# SensorHub.net
KiCad netlist of a schematic drawn in EAGLE
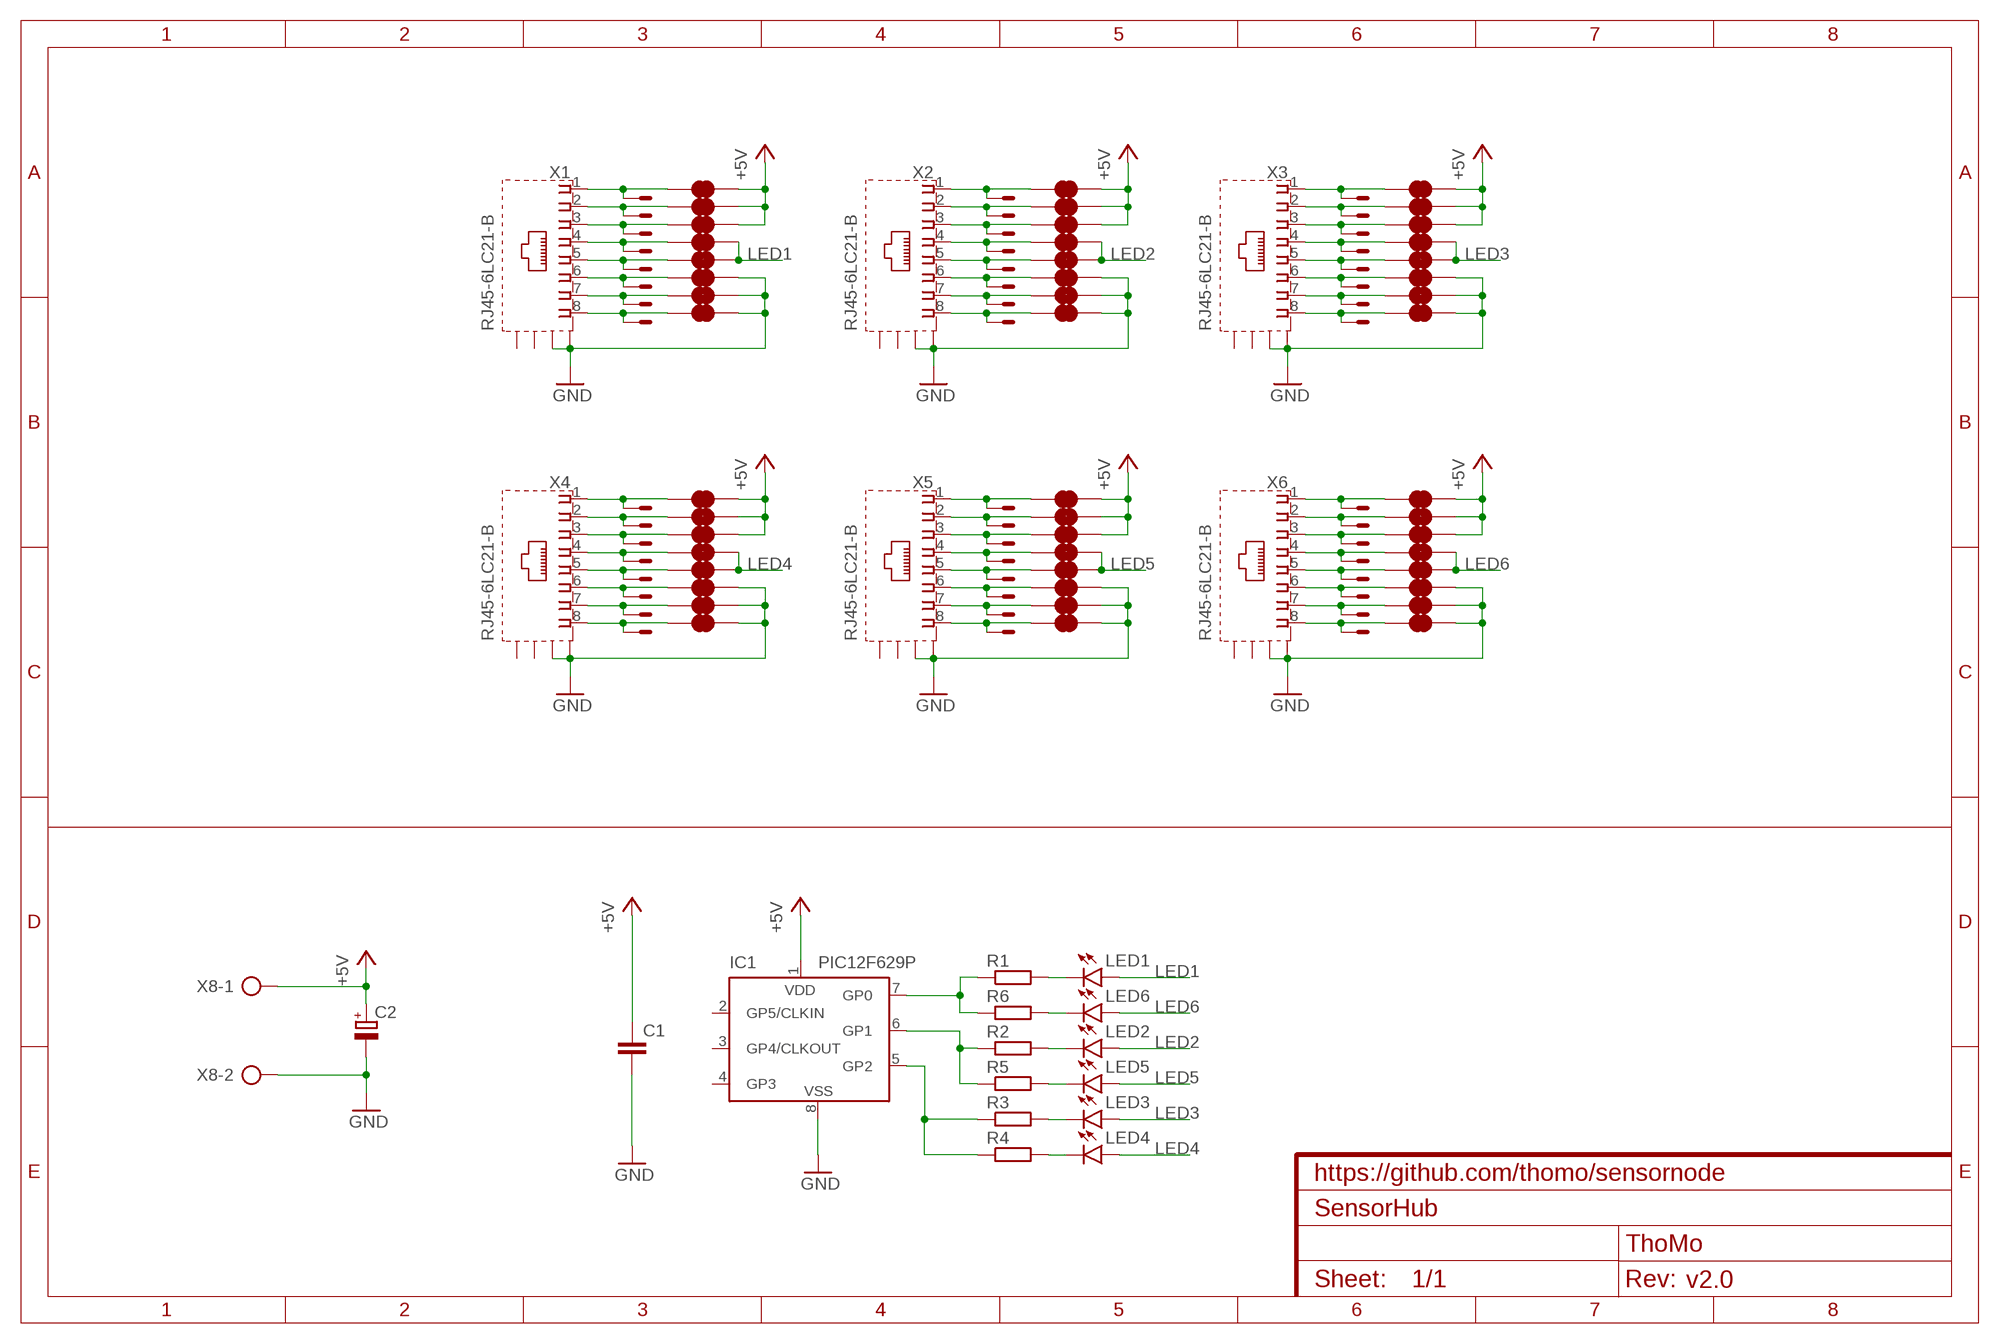
[diagram p0: schematic, sheet 1]

(export (version "E")
  (design (tool "Eeschema 10.0.6"))
  (components
    (comp (ref "C1")
      (value "C-EU050-024X044")
      (footprint "eagle-import:C050-024X044")
      (libsource (lib "eagle-import") (part "C-EU050-024X044"))
    )
    (comp (ref "C2")
      (value "CPOL-EUE3.5-8")
      (footprint "eagle-import:E3,5-8")
      (libsource (lib "eagle-import") (part "CPOL-EUE3.5-8"))
    )
    (comp (ref "IC1")
      (value "PIC12F629P")
      (footprint "eagle-import:DIL8")
      (fields (field (name "MF") "MICROCHIP") (field (name "MPN") "PIC12F629-I/P"))
      (libsource (lib "eagle-import") (part "PIC12F6P29"))
    )
    (comp (ref "JP1")
      (value "JUMPER-SMT_2_NC_TRACE_SILK")
      (footprint "eagle-import:SMT-JUMPER_2_NC_TRACE_SILK")
      (libsource (lib "eagle-import") (part "JUMPER-SMT_2_NC_TRACE_SILK"))
    )
    (comp (ref "JP2")
      (value "JUMPER-SMT_2_NC_TRACE_SILK")
      (footprint "eagle-import:SMT-JUMPER_2_NC_TRACE_SILK")
      (libsource (lib "eagle-import") (part "JUMPER-SMT_2_NC_TRACE_SILK"))
    )
    (comp (ref "JP3")
      (value "JUMPER-SMT_2_NC_TRACE_SILK")
      (footprint "eagle-import:SMT-JUMPER_2_NC_TRACE_SILK")
      (libsource (lib "eagle-import") (part "JUMPER-SMT_2_NC_TRACE_SILK"))
    )
    (comp (ref "JP4")
      (value "JUMPER-SMT_2_NC_TRACE_SILK")
      (footprint "eagle-import:SMT-JUMPER_2_NC_TRACE_SILK")
      (libsource (lib "eagle-import") (part "JUMPER-SMT_2_NC_TRACE_SILK"))
    )
    (comp (ref "JP5")
      (value "JUMPER-SMT_2_NC_TRACE_SILK")
      (footprint "eagle-import:SMT-JUMPER_2_NC_TRACE_SILK")
      (libsource (lib "eagle-import") (part "JUMPER-SMT_2_NC_TRACE_SILK"))
    )
    (comp (ref "JP6")
      (value "JUMPER-SMT_2_NC_TRACE_SILK")
      (footprint "eagle-import:SMT-JUMPER_2_NC_TRACE_SILK")
      (libsource (lib "eagle-import") (part "JUMPER-SMT_2_NC_TRACE_SILK"))
    )
    (comp (ref "JP7")
      (value "JUMPER-SMT_2_NC_TRACE_SILK")
      (footprint "eagle-import:SMT-JUMPER_2_NC_TRACE_SILK")
      (libsource (lib "eagle-import") (part "JUMPER-SMT_2_NC_TRACE_SILK"))
    )
    (comp (ref "JP8")
      (value "JUMPER-SMT_2_NC_TRACE_SILK")
      (footprint "eagle-import:SMT-JUMPER_2_NC_TRACE_SILK")
      (libsource (lib "eagle-import") (part "JUMPER-SMT_2_NC_TRACE_SILK"))
    )
    (comp (ref "JP9")
      (value "JUMPER-SMT_2_NC_TRACE_SILK")
      (footprint "eagle-import:SMT-JUMPER_2_NC_TRACE_SILK")
      (libsource (lib "eagle-import") (part "JUMPER-SMT_2_NC_TRACE_SILK"))
    )
    (comp (ref "JP10")
      (value "JUMPER-SMT_2_NC_TRACE_SILK")
      (footprint "eagle-import:SMT-JUMPER_2_NC_TRACE_SILK")
      (libsource (lib "eagle-import") (part "JUMPER-SMT_2_NC_TRACE_SILK"))
    )
    (comp (ref "JP11")
      (value "JUMPER-SMT_2_NC_TRACE_SILK")
      (footprint "eagle-import:SMT-JUMPER_2_NC_TRACE_SILK")
      (libsource (lib "eagle-import") (part "JUMPER-SMT_2_NC_TRACE_SILK"))
    )
    (comp (ref "JP12")
      (value "JUMPER-SMT_2_NC_TRACE_SILK")
      (footprint "eagle-import:SMT-JUMPER_2_NC_TRACE_SILK")
      (libsource (lib "eagle-import") (part "JUMPER-SMT_2_NC_TRACE_SILK"))
    )
    (comp (ref "JP13")
      (value "JUMPER-SMT_2_NC_TRACE_SILK")
      (footprint "eagle-import:SMT-JUMPER_2_NC_TRACE_SILK")
      (libsource (lib "eagle-import") (part "JUMPER-SMT_2_NC_TRACE_SILK"))
    )
    (comp (ref "JP14")
      (value "JUMPER-SMT_2_NC_TRACE_SILK")
      (footprint "eagle-import:SMT-JUMPER_2_NC_TRACE_SILK")
      (libsource (lib "eagle-import") (part "JUMPER-SMT_2_NC_TRACE_SILK"))
    )
    (comp (ref "JP15")
      (value "JUMPER-SMT_2_NC_TRACE_SILK")
      (footprint "eagle-import:SMT-JUMPER_2_NC_TRACE_SILK")
      (libsource (lib "eagle-import") (part "JUMPER-SMT_2_NC_TRACE_SILK"))
    )
    (comp (ref "JP16")
      (value "JUMPER-SMT_2_NC_TRACE_SILK")
      (footprint "eagle-import:SMT-JUMPER_2_NC_TRACE_SILK")
      (libsource (lib "eagle-import") (part "JUMPER-SMT_2_NC_TRACE_SILK"))
    )
    (comp (ref "JP17")
      (value "JUMPER-SMT_2_NC_TRACE_SILK")
      (footprint "eagle-import:SMT-JUMPER_2_NC_TRACE_SILK")
      (libsource (lib "eagle-import") (part "JUMPER-SMT_2_NC_TRACE_SILK"))
    )
    (comp (ref "JP18")
      (value "JUMPER-SMT_2_NC_TRACE_SILK")
      (footprint "eagle-import:SMT-JUMPER_2_NC_TRACE_SILK")
      (libsource (lib "eagle-import") (part "JUMPER-SMT_2_NC_TRACE_SILK"))
    )
    (comp (ref "JP19")
      (value "JUMPER-SMT_2_NC_TRACE_SILK")
      (footprint "eagle-import:SMT-JUMPER_2_NC_TRACE_SILK")
      (libsource (lib "eagle-import") (part "JUMPER-SMT_2_NC_TRACE_SILK"))
    )
    (comp (ref "JP20")
      (value "JUMPER-SMT_2_NC_TRACE_SILK")
      (footprint "eagle-import:SMT-JUMPER_2_NC_TRACE_SILK")
      (libsource (lib "eagle-import") (part "JUMPER-SMT_2_NC_TRACE_SILK"))
    )
    (comp (ref "JP21")
      (value "JUMPER-SMT_2_NC_TRACE_SILK")
      (footprint "eagle-import:SMT-JUMPER_2_NC_TRACE_SILK")
      (libsource (lib "eagle-import") (part "JUMPER-SMT_2_NC_TRACE_SILK"))
    )
    (comp (ref "JP22")
      (value "JUMPER-SMT_2_NC_TRACE_SILK")
      (footprint "eagle-import:SMT-JUMPER_2_NC_TRACE_SILK")
      (libsource (lib "eagle-import") (part "JUMPER-SMT_2_NC_TRACE_SILK"))
    )
    (comp (ref "JP23")
      (value "JUMPER-SMT_2_NC_TRACE_SILK")
      (footprint "eagle-import:SMT-JUMPER_2_NC_TRACE_SILK")
      (libsource (lib "eagle-import") (part "JUMPER-SMT_2_NC_TRACE_SILK"))
    )
    (comp (ref "JP24")
      (value "JUMPER-SMT_2_NC_TRACE_SILK")
      (footprint "eagle-import:SMT-JUMPER_2_NC_TRACE_SILK")
      (libsource (lib "eagle-import") (part "JUMPER-SMT_2_NC_TRACE_SILK"))
    )
    (comp (ref "JP25")
      (value "JUMPER-SMT_2_NC_TRACE_SILK")
      (footprint "eagle-import:SMT-JUMPER_2_NC_TRACE_SILK")
      (libsource (lib "eagle-import") (part "JUMPER-SMT_2_NC_TRACE_SILK"))
    )
    (comp (ref "JP26")
      (value "JUMPER-SMT_2_NC_TRACE_SILK")
      (footprint "eagle-import:SMT-JUMPER_2_NC_TRACE_SILK")
      (libsource (lib "eagle-import") (part "JUMPER-SMT_2_NC_TRACE_SILK"))
    )
    (comp (ref "JP27")
      (value "JUMPER-SMT_2_NC_TRACE_SILK")
      (footprint "eagle-import:SMT-JUMPER_2_NC_TRACE_SILK")
      (libsource (lib "eagle-import") (part "JUMPER-SMT_2_NC_TRACE_SILK"))
    )
    (comp (ref "JP28")
      (value "JUMPER-SMT_2_NC_TRACE_SILK")
      (footprint "eagle-import:SMT-JUMPER_2_NC_TRACE_SILK")
      (libsource (lib "eagle-import") (part "JUMPER-SMT_2_NC_TRACE_SILK"))
    )
    (comp (ref "JP29")
      (value "JUMPER-SMT_2_NC_TRACE_SILK")
      (footprint "eagle-import:SMT-JUMPER_2_NC_TRACE_SILK")
      (libsource (lib "eagle-import") (part "JUMPER-SMT_2_NC_TRACE_SILK"))
    )
    (comp (ref "JP30")
      (value "JUMPER-SMT_2_NC_TRACE_SILK")
      (footprint "eagle-import:SMT-JUMPER_2_NC_TRACE_SILK")
      (libsource (lib "eagle-import") (part "JUMPER-SMT_2_NC_TRACE_SILK"))
    )
    (comp (ref "JP31")
      (value "JUMPER-SMT_2_NC_TRACE_SILK")
      (footprint "eagle-import:SMT-JUMPER_2_NC_TRACE_SILK")
      (libsource (lib "eagle-import") (part "JUMPER-SMT_2_NC_TRACE_SILK"))
    )
    (comp (ref "JP32")
      (value "JUMPER-SMT_2_NC_TRACE_SILK")
      (footprint "eagle-import:SMT-JUMPER_2_NC_TRACE_SILK")
      (libsource (lib "eagle-import") (part "JUMPER-SMT_2_NC_TRACE_SILK"))
    )
    (comp (ref "JP33")
      (value "JUMPER-SMT_2_NC_TRACE_SILK")
      (footprint "eagle-import:SMT-JUMPER_2_NC_TRACE_SILK")
      (libsource (lib "eagle-import") (part "JUMPER-SMT_2_NC_TRACE_SILK"))
    )
    (comp (ref "JP34")
      (value "JUMPER-SMT_2_NC_TRACE_SILK")
      (footprint "eagle-import:SMT-JUMPER_2_NC_TRACE_SILK")
      (libsource (lib "eagle-import") (part "JUMPER-SMT_2_NC_TRACE_SILK"))
    )
    (comp (ref "JP35")
      (value "JUMPER-SMT_2_NC_TRACE_SILK")
      (footprint "eagle-import:SMT-JUMPER_2_NC_TRACE_SILK")
      (libsource (lib "eagle-import") (part "JUMPER-SMT_2_NC_TRACE_SILK"))
    )
    (comp (ref "JP36")
      (value "JUMPER-SMT_2_NC_TRACE_SILK")
      (footprint "eagle-import:SMT-JUMPER_2_NC_TRACE_SILK")
      (libsource (lib "eagle-import") (part "JUMPER-SMT_2_NC_TRACE_SILK"))
    )
    (comp (ref "JP37")
      (value "JUMPER-SMT_2_NC_TRACE_SILK")
      (footprint "eagle-import:SMT-JUMPER_2_NC_TRACE_SILK")
      (libsource (lib "eagle-import") (part "JUMPER-SMT_2_NC_TRACE_SILK"))
    )
    (comp (ref "JP38")
      (value "JUMPER-SMT_2_NC_TRACE_SILK")
      (footprint "eagle-import:SMT-JUMPER_2_NC_TRACE_SILK")
      (libsource (lib "eagle-import") (part "JUMPER-SMT_2_NC_TRACE_SILK"))
    )
    (comp (ref "JP39")
      (value "JUMPER-SMT_2_NC_TRACE_SILK")
      (footprint "eagle-import:SMT-JUMPER_2_NC_TRACE_SILK")
      (libsource (lib "eagle-import") (part "JUMPER-SMT_2_NC_TRACE_SILK"))
    )
    (comp (ref "JP40")
      (value "JUMPER-SMT_2_NC_TRACE_SILK")
      (footprint "eagle-import:SMT-JUMPER_2_NC_TRACE_SILK")
      (libsource (lib "eagle-import") (part "JUMPER-SMT_2_NC_TRACE_SILK"))
    )
    (comp (ref "JP41")
      (value "JUMPER-SMT_2_NC_TRACE_SILK")
      (footprint "eagle-import:SMT-JUMPER_2_NC_TRACE_SILK")
      (libsource (lib "eagle-import") (part "JUMPER-SMT_2_NC_TRACE_SILK"))
    )
    (comp (ref "JP42")
      (value "JUMPER-SMT_2_NC_TRACE_SILK")
      (footprint "eagle-import:SMT-JUMPER_2_NC_TRACE_SILK")
      (libsource (lib "eagle-import") (part "JUMPER-SMT_2_NC_TRACE_SILK"))
    )
    (comp (ref "JP43")
      (value "JUMPER-SMT_2_NC_TRACE_SILK")
      (footprint "eagle-import:SMT-JUMPER_2_NC_TRACE_SILK")
      (libsource (lib "eagle-import") (part "JUMPER-SMT_2_NC_TRACE_SILK"))
    )
    (comp (ref "JP44")
      (value "JUMPER-SMT_2_NC_TRACE_SILK")
      (footprint "eagle-import:SMT-JUMPER_2_NC_TRACE_SILK")
      (libsource (lib "eagle-import") (part "JUMPER-SMT_2_NC_TRACE_SILK"))
    )
    (comp (ref "JP45")
      (value "JUMPER-SMT_2_NC_TRACE_SILK")
      (footprint "eagle-import:SMT-JUMPER_2_NC_TRACE_SILK")
      (libsource (lib "eagle-import") (part "JUMPER-SMT_2_NC_TRACE_SILK"))
    )
    (comp (ref "JP46")
      (value "JUMPER-SMT_2_NC_TRACE_SILK")
      (footprint "eagle-import:SMT-JUMPER_2_NC_TRACE_SILK")
      (libsource (lib "eagle-import") (part "JUMPER-SMT_2_NC_TRACE_SILK"))
    )
    (comp (ref "JP47")
      (value "JUMPER-SMT_2_NC_TRACE_SILK")
      (footprint "eagle-import:SMT-JUMPER_2_NC_TRACE_SILK")
      (libsource (lib "eagle-import") (part "JUMPER-SMT_2_NC_TRACE_SILK"))
    )
    (comp (ref "JP48")
      (value "JUMPER-SMT_2_NC_TRACE_SILK")
      (footprint "eagle-import:SMT-JUMPER_2_NC_TRACE_SILK")
      (libsource (lib "eagle-import") (part "JUMPER-SMT_2_NC_TRACE_SILK"))
    )
    (comp (ref "LED1")
      (value "TLLR4400")
      (footprint "eagle-import:LED3MM")
      (fields (field (name "MF") "VISHAY SEMICONDUCTOR"))
      (libsource (lib "eagle-import") (part "TLLR4400"))
    )
    (comp (ref "LED2")
      (value "TLLR4400")
      (footprint "eagle-import:LED3MM")
      (fields (field (name "MF") "VISHAY SEMICONDUCTOR"))
      (libsource (lib "eagle-import") (part "TLLR4400"))
    )
    (comp (ref "LED3")
      (value "TLLR4400")
      (footprint "eagle-import:LED3MM")
      (fields (field (name "MF") "VISHAY SEMICONDUCTOR"))
      (libsource (lib "eagle-import") (part "TLLR4400"))
    )
    (comp (ref "LED4")
      (value "TLLR4400")
      (footprint "eagle-import:LED3MM")
      (fields (field (name "MF") "VISHAY SEMICONDUCTOR"))
      (libsource (lib "eagle-import") (part "TLLR4400"))
    )
    (comp (ref "LED5")
      (value "TLLR4400")
      (footprint "eagle-import:LED3MM")
      (fields (field (name "MF") "VISHAY SEMICONDUCTOR"))
      (libsource (lib "eagle-import") (part "TLLR4400"))
    )
    (comp (ref "LED6")
      (value "TLLR4400")
      (footprint "eagle-import:LED3MM")
      (fields (field (name "MF") "VISHAY SEMICONDUCTOR"))
      (libsource (lib "eagle-import") (part "TLLR4400"))
    )
    (comp (ref "R1")
      (value "R-EU_0207/10")
      (footprint "eagle-import:0207_10")
      (libsource (lib "eagle-import") (part "R-EU_0207/10"))
    )
    (comp (ref "R2")
      (value "R-EU_0207/10")
      (footprint "eagle-import:0207_10")
      (libsource (lib "eagle-import") (part "R-EU_0207/10"))
    )
    (comp (ref "R3")
      (value "R-EU_0207/10")
      (footprint "eagle-import:0207_10")
      (libsource (lib "eagle-import") (part "R-EU_0207/10"))
    )
    (comp (ref "R4")
      (value "R-EU_0207/10")
      (footprint "eagle-import:0207_10")
      (libsource (lib "eagle-import") (part "R-EU_0207/10"))
    )
    (comp (ref "R5")
      (value "R-EU_0207/10")
      (footprint "eagle-import:0207_10")
      (libsource (lib "eagle-import") (part "R-EU_0207/10"))
    )
    (comp (ref "R6")
      (value "R-EU_0207/10")
      (footprint "eagle-import:0207_10")
      (libsource (lib "eagle-import") (part "R-EU_0207/10"))
    )
    (comp (ref "X1")
      (value "RJ45-6LC21-B")
      (footprint "eagle-import:RJ45-SHIELD1")
      (libsource (lib "eagle-import") (part "RJ4521-B-6LC"))
    )
    (comp (ref "X1.1")
      (value "22-23-2081")
      (footprint "eagle-import:22-23-2081")
      (fields (field (name "MF") "MOLEX"))
      (libsource (lib "eagle-import") (part "22-23-2081"))
    )
    (comp (ref "X1.2")
      (value "22-23-2081")
      (footprint "eagle-import:22-23-2081")
      (fields (field (name "MF") "MOLEX"))
      (libsource (lib "eagle-import") (part "22-23-2081"))
    )
    (comp (ref "X1.3")
      (value "22-23-2081")
      (footprint "eagle-import:22-23-2081")
      (fields (field (name "MF") "MOLEX"))
      (libsource (lib "eagle-import") (part "22-23-2081"))
    )
    (comp (ref "X1.4")
      (value "22-23-2081")
      (footprint "eagle-import:22-23-2081")
      (fields (field (name "MF") "MOLEX"))
      (libsource (lib "eagle-import") (part "22-23-2081"))
    )
    (comp (ref "X1.5")
      (value "22-23-2081")
      (footprint "eagle-import:22-23-2081")
      (fields (field (name "MF") "MOLEX"))
      (libsource (lib "eagle-import") (part "22-23-2081"))
    )
    (comp (ref "X1.6")
      (value "22-23-2081")
      (footprint "eagle-import:22-23-2081")
      (fields (field (name "MF") "MOLEX"))
      (libsource (lib "eagle-import") (part "22-23-2081"))
    )
    (comp (ref "X2")
      (value "RJ45-6LC21-B")
      (footprint "eagle-import:RJ45-SHIELD1")
      (libsource (lib "eagle-import") (part "RJ4521-B-6LC"))
    )
    (comp (ref "X3")
      (value "RJ45-6LC21-B")
      (footprint "eagle-import:RJ45-SHIELD1")
      (libsource (lib "eagle-import") (part "RJ4521-B-6LC"))
    )
    (comp (ref "X4")
      (value "RJ45-6LC21-B")
      (footprint "eagle-import:RJ45-SHIELD1")
      (libsource (lib "eagle-import") (part "RJ4521-B-6LC"))
    )
    (comp (ref "X5")
      (value "RJ45-6LC21-B")
      (footprint "eagle-import:RJ45-SHIELD1")
      (libsource (lib "eagle-import") (part "RJ4521-B-6LC"))
    )
    (comp (ref "X6")
      (value "RJ45-6LC21-B")
      (footprint "eagle-import:RJ45-SHIELD1")
      (libsource (lib "eagle-import") (part "RJ4521-B-6LC"))
    )
    (comp (ref "X8")
      (value "AK500/2")
      (footprint "eagle-import:AK500_2")
      (libsource (lib "eagle-import") (part "AK500/2"))
    )
  )
  (nets
    (net (code "1") (name "+5V") (class "Default")
      (node (ref "C1") (pin "1") (pinfunction "1_1") (pintype "passive"))
      (node (ref "C2") (pin "+") (pinfunction "+_+") (pintype "passive"))
      (node (ref "IC1") (pin "1") (pinfunction "VDD_1") (pintype "power_in"))
      (node (ref "JP1") (pin "2") (pinfunction "2_2") (pintype "passive"))
      (node (ref "JP10") (pin "2") (pinfunction "2_2") (pintype "passive"))
      (node (ref "JP11") (pin "2") (pinfunction "2_2") (pintype "passive"))
      (node (ref "JP17") (pin "2") (pinfunction "2_2") (pintype "passive"))
      (node (ref "JP18") (pin "2") (pinfunction "2_2") (pintype "passive"))
      (node (ref "JP19") (pin "2") (pinfunction "2_2") (pintype "passive"))
      (node (ref "JP2") (pin "2") (pinfunction "2_2") (pintype "passive"))
      (node (ref "JP25") (pin "2") (pinfunction "2_2") (pintype "passive"))
      (node (ref "JP26") (pin "2") (pinfunction "2_2") (pintype "passive"))
      (node (ref "JP27") (pin "2") (pinfunction "2_2") (pintype "passive"))
      (node (ref "JP3") (pin "2") (pinfunction "2_2") (pintype "passive"))
      (node (ref "JP33") (pin "2") (pinfunction "2_2") (pintype "passive"))
      (node (ref "JP34") (pin "2") (pinfunction "2_2") (pintype "passive"))
      (node (ref "JP35") (pin "2") (pinfunction "2_2") (pintype "passive"))
      (node (ref "JP41") (pin "2") (pinfunction "2_2") (pintype "passive"))
      (node (ref "JP42") (pin "2") (pinfunction "2_2") (pintype "passive"))
      (node (ref "JP43") (pin "2") (pinfunction "2_2") (pintype "passive"))
      (node (ref "JP9") (pin "2") (pinfunction "2_2") (pintype "passive"))
      (node (ref "X8") (pin "1") (pinfunction "KL_1") (pintype "passive"))
    )
    (net (code "2") (name "/LED1") (class "Default")
      (node (ref "JP4") (pin "2") (pinfunction "2_2") (pintype "passive"))
      (node (ref "JP5") (pin "2") (pinfunction "2_2") (pintype "passive"))
      (node (ref "LED1") (pin "A") (pinfunction "A_A") (pintype "passive"))
    )
    (net (code "3") (name "/LED2") (class "Default")
      (node (ref "JP12") (pin "2") (pinfunction "2_2") (pintype "passive"))
      (node (ref "JP13") (pin "2") (pinfunction "2_2") (pintype "passive"))
      (node (ref "LED2") (pin "A") (pinfunction "A_A") (pintype "passive"))
    )
    (net (code "4") (name "/LED3") (class "Default")
      (node (ref "JP20") (pin "2") (pinfunction "2_2") (pintype "passive"))
      (node (ref "JP21") (pin "2") (pinfunction "2_2") (pintype "passive"))
      (node (ref "LED3") (pin "A") (pinfunction "A_A") (pintype "passive"))
    )
    (net (code "5") (name "/LED4") (class "Default")
      (node (ref "JP28") (pin "2") (pinfunction "2_2") (pintype "passive"))
      (node (ref "JP29") (pin "2") (pinfunction "2_2") (pintype "passive"))
      (node (ref "LED4") (pin "A") (pinfunction "A_A") (pintype "passive"))
    )
    (net (code "6") (name "/LED5") (class "Default")
      (node (ref "JP36") (pin "2") (pinfunction "2_2") (pintype "passive"))
      (node (ref "JP37") (pin "2") (pinfunction "2_2") (pintype "passive"))
      (node (ref "LED5") (pin "A") (pinfunction "A_A") (pintype "passive"))
    )
    (net (code "7") (name "/LED6") (class "Default")
      (node (ref "JP44") (pin "2") (pinfunction "2_2") (pintype "passive"))
      (node (ref "JP45") (pin "2") (pinfunction "2_2") (pintype "passive"))
      (node (ref "LED6") (pin "A") (pinfunction "A_A") (pintype "passive"))
    )
    (net (code "8") (name "GND") (class "Default")
      (node (ref "C1") (pin "2") (pinfunction "2_2") (pintype "passive"))
      (node (ref "C2") (pin "-") (pinfunction "-_-") (pintype "passive"))
      (node (ref "IC1") (pin "8") (pinfunction "VSS_8") (pintype "power_in"))
      (node (ref "JP14") (pin "2") (pinfunction "2_2") (pintype "passive"))
      (node (ref "JP15") (pin "2") (pinfunction "2_2") (pintype "passive"))
      (node (ref "JP16") (pin "2") (pinfunction "2_2") (pintype "passive"))
      (node (ref "JP22") (pin "2") (pinfunction "2_2") (pintype "passive"))
      (node (ref "JP23") (pin "2") (pinfunction "2_2") (pintype "passive"))
      (node (ref "JP24") (pin "2") (pinfunction "2_2") (pintype "passive"))
      (node (ref "JP30") (pin "2") (pinfunction "2_2") (pintype "passive"))
      (node (ref "JP31") (pin "2") (pinfunction "2_2") (pintype "passive"))
      (node (ref "JP32") (pin "2") (pinfunction "2_2") (pintype "passive"))
      (node (ref "JP38") (pin "2") (pinfunction "2_2") (pintype "passive"))
      (node (ref "JP39") (pin "2") (pinfunction "2_2") (pintype "passive"))
      (node (ref "JP40") (pin "2") (pinfunction "2_2") (pintype "passive"))
      (node (ref "JP46") (pin "2") (pinfunction "2_2") (pintype "passive"))
      (node (ref "JP47") (pin "2") (pinfunction "2_2") (pintype "passive"))
      (node (ref "JP48") (pin "2") (pinfunction "2_2") (pintype "passive"))
      (node (ref "JP6") (pin "2") (pinfunction "2_2") (pintype "passive"))
      (node (ref "JP7") (pin "2") (pinfunction "2_2") (pintype "passive"))
      (node (ref "JP8") (pin "2") (pinfunction "2_2") (pintype "passive"))
      (node (ref "X1") (pin "S1") (pinfunction "S_S1") (pintype "passive"))
      (node (ref "X1") (pin "S2") (pinfunction "S_S2") (pintype "passive"))
      (node (ref "X2") (pin "S1") (pinfunction "S_S1") (pintype "passive"))
      (node (ref "X2") (pin "S2") (pinfunction "S_S2") (pintype "passive"))
      (node (ref "X3") (pin "S1") (pinfunction "S_S1") (pintype "passive"))
      (node (ref "X3") (pin "S2") (pinfunction "S_S2") (pintype "passive"))
      (node (ref "X4") (pin "S1") (pinfunction "S_S1") (pintype "passive"))
      (node (ref "X4") (pin "S2") (pinfunction "S_S2") (pintype "passive"))
      (node (ref "X5") (pin "S1") (pinfunction "S_S1") (pintype "passive"))
      (node (ref "X5") (pin "S2") (pinfunction "S_S2") (pintype "passive"))
      (node (ref "X6") (pin "S1") (pinfunction "S_S1") (pintype "passive"))
      (node (ref "X6") (pin "S2") (pinfunction "S_S2") (pintype "passive"))
      (node (ref "X8") (pin "2") (pinfunction "KL_2") (pintype "passive"))
    )
    (net (code "9") (name "Net-(IC1-GP0)") (class "Default")
      (node (ref "IC1") (pin "7") (pinfunction "GP0_7") (pintype "bidirectional"))
      (node (ref "R1") (pin "1") (pinfunction "1_1") (pintype "passive"))
      (node (ref "R6") (pin "1") (pinfunction "1_1") (pintype "passive"))
    )
    (net (code "10") (name "Net-(IC1-GP1)") (class "Default")
      (node (ref "IC1") (pin "6") (pinfunction "GP1_6") (pintype "bidirectional"))
      (node (ref "R2") (pin "1") (pinfunction "1_1") (pintype "passive"))
      (node (ref "R5") (pin "1") (pinfunction "1_1") (pintype "passive"))
    )
    (net (code "11") (name "Net-(IC1-GP2)") (class "Default")
      (node (ref "IC1") (pin "5") (pinfunction "GP2_5") (pintype "bidirectional"))
      (node (ref "R3") (pin "1") (pinfunction "1_1") (pintype "passive"))
      (node (ref "R4") (pin "1") (pinfunction "1_1") (pintype "passive"))
    )
    (net (code "12") (name "Net-(LED1-C)") (class "Default")
      (node (ref "LED1") (pin "K") (pinfunction "C_K") (pintype "passive"))
      (node (ref "R1") (pin "2") (pinfunction "2_2") (pintype "passive"))
    )
    (net (code "13") (name "Net-(LED2-C)") (class "Default")
      (node (ref "LED2") (pin "K") (pinfunction "C_K") (pintype "passive"))
      (node (ref "R2") (pin "2") (pinfunction "2_2") (pintype "passive"))
    )
    (net (code "14") (name "Net-(LED3-C)") (class "Default")
      (node (ref "LED3") (pin "K") (pinfunction "C_K") (pintype "passive"))
      (node (ref "R3") (pin "2") (pinfunction "2_2") (pintype "passive"))
    )
    (net (code "15") (name "Net-(LED4-C)") (class "Default")
      (node (ref "LED4") (pin "K") (pinfunction "C_K") (pintype "passive"))
      (node (ref "R4") (pin "2") (pinfunction "2_2") (pintype "passive"))
    )
    (net (code "16") (name "Net-(LED5-C)") (class "Default")
      (node (ref "LED5") (pin "K") (pinfunction "C_K") (pintype "passive"))
      (node (ref "R5") (pin "2") (pinfunction "2_2") (pintype "passive"))
    )
    (net (code "17") (name "Net-(LED6-C)") (class "Default")
      (node (ref "LED6") (pin "K") (pinfunction "C_K") (pintype "passive"))
      (node (ref "R6") (pin "2") (pinfunction "2_2") (pintype "passive"))
    )
    (net (code "18") (name "Net-(X1.1A-S)") (class "Default")
      (node (ref "JP1") (pin "1") (pinfunction "1_1") (pintype "passive"))
      (node (ref "X1") (pin "1") (pinfunction "1_1") (pintype "passive"))
      (node (ref "X1.1") (pin "1") (pinfunction "S_1") (pintype "passive"))
    )
    (net (code "19") (name "Net-(X1.1B-S)") (class "Default")
      (node (ref "JP2") (pin "1") (pinfunction "1_1") (pintype "passive"))
      (node (ref "X1") (pin "2") (pinfunction "2_2") (pintype "passive"))
      (node (ref "X1.1") (pin "2") (pinfunction "S_2") (pintype "passive"))
    )
    (net (code "20") (name "Net-(X1.1C-S)") (class "Default")
      (node (ref "JP3") (pin "1") (pinfunction "1_1") (pintype "passive"))
      (node (ref "X1") (pin "3") (pinfunction "3_3") (pintype "passive"))
      (node (ref "X1.1") (pin "3") (pinfunction "S_3") (pintype "passive"))
    )
    (net (code "21") (name "Net-(X1.1D-S)") (class "Default")
      (node (ref "JP4") (pin "1") (pinfunction "1_1") (pintype "passive"))
      (node (ref "X1") (pin "4") (pinfunction "4_4") (pintype "passive"))
      (node (ref "X1.1") (pin "4") (pinfunction "S_4") (pintype "passive"))
    )
    (net (code "22") (name "Net-(X1.1E-S)") (class "Default")
      (node (ref "JP5") (pin "1") (pinfunction "1_1") (pintype "passive"))
      (node (ref "X1") (pin "5") (pinfunction "5_5") (pintype "passive"))
      (node (ref "X1.1") (pin "5") (pinfunction "S_5") (pintype "passive"))
    )
    (net (code "23") (name "Net-(X1.1F-S)") (class "Default")
      (node (ref "JP6") (pin "1") (pinfunction "1_1") (pintype "passive"))
      (node (ref "X1") (pin "6") (pinfunction "6_6") (pintype "passive"))
      (node (ref "X1.1") (pin "6") (pinfunction "S_6") (pintype "passive"))
    )
    (net (code "24") (name "Net-(X1.1G-S)") (class "Default")
      (node (ref "JP7") (pin "1") (pinfunction "1_1") (pintype "passive"))
      (node (ref "X1") (pin "7") (pinfunction "7_7") (pintype "passive"))
      (node (ref "X1.1") (pin "7") (pinfunction "S_7") (pintype "passive"))
    )
    (net (code "25") (name "Net-(X1.1H-S)") (class "Default")
      (node (ref "JP8") (pin "1") (pinfunction "1_1") (pintype "passive"))
      (node (ref "X1") (pin "8") (pinfunction "8_8") (pintype "passive"))
      (node (ref "X1.1") (pin "8") (pinfunction "S_8") (pintype "passive"))
    )
    (net (code "26") (name "Net-(X1.2A-S)") (class "Default")
      (node (ref "JP9") (pin "1") (pinfunction "1_1") (pintype "passive"))
      (node (ref "X1.2") (pin "1") (pinfunction "S_1") (pintype "passive"))
      (node (ref "X2") (pin "1") (pinfunction "1_1") (pintype "passive"))
    )
    (net (code "27") (name "Net-(X1.2B-S)") (class "Default")
      (node (ref "JP10") (pin "1") (pinfunction "1_1") (pintype "passive"))
      (node (ref "X1.2") (pin "2") (pinfunction "S_2") (pintype "passive"))
      (node (ref "X2") (pin "2") (pinfunction "2_2") (pintype "passive"))
    )
    (net (code "28") (name "Net-(X1.2C-S)") (class "Default")
      (node (ref "JP11") (pin "1") (pinfunction "1_1") (pintype "passive"))
      (node (ref "X1.2") (pin "3") (pinfunction "S_3") (pintype "passive"))
      (node (ref "X2") (pin "3") (pinfunction "3_3") (pintype "passive"))
    )
    (net (code "29") (name "Net-(X1.2D-S)") (class "Default")
      (node (ref "JP12") (pin "1") (pinfunction "1_1") (pintype "passive"))
      (node (ref "X1.2") (pin "4") (pinfunction "S_4") (pintype "passive"))
      (node (ref "X2") (pin "4") (pinfunction "4_4") (pintype "passive"))
    )
    (net (code "30") (name "Net-(X1.2E-S)") (class "Default")
      (node (ref "JP13") (pin "1") (pinfunction "1_1") (pintype "passive"))
      (node (ref "X1.2") (pin "5") (pinfunction "S_5") (pintype "passive"))
      (node (ref "X2") (pin "5") (pinfunction "5_5") (pintype "passive"))
    )
    (net (code "31") (name "Net-(X1.2F-S)") (class "Default")
      (node (ref "JP14") (pin "1") (pinfunction "1_1") (pintype "passive"))
      (node (ref "X1.2") (pin "6") (pinfunction "S_6") (pintype "passive"))
      (node (ref "X2") (pin "6") (pinfunction "6_6") (pintype "passive"))
    )
    (net (code "32") (name "Net-(X1.2G-S)") (class "Default")
      (node (ref "JP15") (pin "1") (pinfunction "1_1") (pintype "passive"))
      (node (ref "X1.2") (pin "7") (pinfunction "S_7") (pintype "passive"))
      (node (ref "X2") (pin "7") (pinfunction "7_7") (pintype "passive"))
    )
    (net (code "33") (name "Net-(X1.2H-S)") (class "Default")
      (node (ref "JP16") (pin "1") (pinfunction "1_1") (pintype "passive"))
      (node (ref "X1.2") (pin "8") (pinfunction "S_8") (pintype "passive"))
      (node (ref "X2") (pin "8") (pinfunction "8_8") (pintype "passive"))
    )
    (net (code "34") (name "Net-(X1.3A-S)") (class "Default")
      (node (ref "JP17") (pin "1") (pinfunction "1_1") (pintype "passive"))
      (node (ref "X1.3") (pin "1") (pinfunction "S_1") (pintype "passive"))
      (node (ref "X3") (pin "1") (pinfunction "1_1") (pintype "passive"))
    )
    (net (code "35") (name "Net-(X1.3B-S)") (class "Default")
      (node (ref "JP18") (pin "1") (pinfunction "1_1") (pintype "passive"))
      (node (ref "X1.3") (pin "2") (pinfunction "S_2") (pintype "passive"))
      (node (ref "X3") (pin "2") (pinfunction "2_2") (pintype "passive"))
    )
    (net (code "36") (name "Net-(X1.3C-S)") (class "Default")
      (node (ref "JP19") (pin "1") (pinfunction "1_1") (pintype "passive"))
      (node (ref "X1.3") (pin "3") (pinfunction "S_3") (pintype "passive"))
      (node (ref "X3") (pin "3") (pinfunction "3_3") (pintype "passive"))
    )
    (net (code "37") (name "Net-(X1.3D-S)") (class "Default")
      (node (ref "JP20") (pin "1") (pinfunction "1_1") (pintype "passive"))
      (node (ref "X1.3") (pin "4") (pinfunction "S_4") (pintype "passive"))
      (node (ref "X3") (pin "4") (pinfunction "4_4") (pintype "passive"))
    )
    (net (code "38") (name "Net-(X1.3E-S)") (class "Default")
      (node (ref "JP21") (pin "1") (pinfunction "1_1") (pintype "passive"))
      (node (ref "X1.3") (pin "5") (pinfunction "S_5") (pintype "passive"))
      (node (ref "X3") (pin "5") (pinfunction "5_5") (pintype "passive"))
    )
    (net (code "39") (name "Net-(X1.3F-S)") (class "Default")
      (node (ref "JP22") (pin "1") (pinfunction "1_1") (pintype "passive"))
      (node (ref "X1.3") (pin "6") (pinfunction "S_6") (pintype "passive"))
      (node (ref "X3") (pin "6") (pinfunction "6_6") (pintype "passive"))
    )
    (net (code "40") (name "Net-(X1.3G-S)") (class "Default")
      (node (ref "JP23") (pin "1") (pinfunction "1_1") (pintype "passive"))
      (node (ref "X1.3") (pin "7") (pinfunction "S_7") (pintype "passive"))
      (node (ref "X3") (pin "7") (pinfunction "7_7") (pintype "passive"))
    )
    (net (code "41") (name "Net-(X1.3H-S)") (class "Default")
      (node (ref "JP24") (pin "1") (pinfunction "1_1") (pintype "passive"))
      (node (ref "X1.3") (pin "8") (pinfunction "S_8") (pintype "passive"))
      (node (ref "X3") (pin "8") (pinfunction "8_8") (pintype "passive"))
    )
    (net (code "42") (name "Net-(X1.4A-S)") (class "Default")
      (node (ref "JP25") (pin "1") (pinfunction "1_1") (pintype "passive"))
      (node (ref "X1.4") (pin "1") (pinfunction "S_1") (pintype "passive"))
      (node (ref "X4") (pin "1") (pinfunction "1_1") (pintype "passive"))
    )
    (net (code "43") (name "Net-(X1.4B-S)") (class "Default")
      (node (ref "JP26") (pin "1") (pinfunction "1_1") (pintype "passive"))
      (node (ref "X1.4") (pin "2") (pinfunction "S_2") (pintype "passive"))
      (node (ref "X4") (pin "2") (pinfunction "2_2") (pintype "passive"))
    )
    (net (code "44") (name "Net-(X1.4C-S)") (class "Default")
      (node (ref "JP27") (pin "1") (pinfunction "1_1") (pintype "passive"))
      (node (ref "X1.4") (pin "3") (pinfunction "S_3") (pintype "passive"))
      (node (ref "X4") (pin "3") (pinfunction "3_3") (pintype "passive"))
    )
    (net (code "45") (name "Net-(X1.4D-S)") (class "Default")
      (node (ref "JP28") (pin "1") (pinfunction "1_1") (pintype "passive"))
      (node (ref "X1.4") (pin "4") (pinfunction "S_4") (pintype "passive"))
      (node (ref "X4") (pin "4") (pinfunction "4_4") (pintype "passive"))
    )
    (net (code "46") (name "Net-(X1.4E-S)") (class "Default")
      (node (ref "JP29") (pin "1") (pinfunction "1_1") (pintype "passive"))
      (node (ref "X1.4") (pin "5") (pinfunction "S_5") (pintype "passive"))
      (node (ref "X4") (pin "5") (pinfunction "5_5") (pintype "passive"))
    )
    (net (code "47") (name "Net-(X1.4F-S)") (class "Default")
      (node (ref "JP30") (pin "1") (pinfunction "1_1") (pintype "passive"))
      (node (ref "X1.4") (pin "6") (pinfunction "S_6") (pintype "passive"))
      (node (ref "X4") (pin "6") (pinfunction "6_6") (pintype "passive"))
    )
    (net (code "48") (name "Net-(X1.4G-S)") (class "Default")
      (node (ref "JP31") (pin "1") (pinfunction "1_1") (pintype "passive"))
      (node (ref "X1.4") (pin "7") (pinfunction "S_7") (pintype "passive"))
      (node (ref "X4") (pin "7") (pinfunction "7_7") (pintype "passive"))
    )
    (net (code "49") (name "Net-(X1.4H-S)") (class "Default")
      (node (ref "JP32") (pin "1") (pinfunction "1_1") (pintype "passive"))
      (node (ref "X1.4") (pin "8") (pinfunction "S_8") (pintype "passive"))
      (node (ref "X4") (pin "8") (pinfunction "8_8") (pintype "passive"))
    )
    (net (code "50") (name "Net-(X1.5A-S)") (class "Default")
      (node (ref "JP33") (pin "1") (pinfunction "1_1") (pintype "passive"))
      (node (ref "X1.5") (pin "1") (pinfunction "S_1") (pintype "passive"))
      (node (ref "X5") (pin "1") (pinfunction "1_1") (pintype "passive"))
    )
    (net (code "51") (name "Net-(X1.5B-S)") (class "Default")
      (node (ref "JP34") (pin "1") (pinfunction "1_1") (pintype "passive"))
      (node (ref "X1.5") (pin "2") (pinfunction "S_2") (pintype "passive"))
      (node (ref "X5") (pin "2") (pinfunction "2_2") (pintype "passive"))
    )
    (net (code "52") (name "Net-(X1.5C-S)") (class "Default")
      (node (ref "JP35") (pin "1") (pinfunction "1_1") (pintype "passive"))
      (node (ref "X1.5") (pin "3") (pinfunction "S_3") (pintype "passive"))
      (node (ref "X5") (pin "3") (pinfunction "3_3") (pintype "passive"))
    )
    (net (code "53") (name "Net-(X1.5D-S)") (class "Default")
      (node (ref "JP36") (pin "1") (pinfunction "1_1") (pintype "passive"))
      (node (ref "X1.5") (pin "4") (pinfunction "S_4") (pintype "passive"))
      (node (ref "X5") (pin "4") (pinfunction "4_4") (pintype "passive"))
    )
    (net (code "54") (name "Net-(X1.5E-S)") (class "Default")
      (node (ref "JP37") (pin "1") (pinfunction "1_1") (pintype "passive"))
      (node (ref "X1.5") (pin "5") (pinfunction "S_5") (pintype "passive"))
      (node (ref "X5") (pin "5") (pinfunction "5_5") (pintype "passive"))
    )
    (net (code "55") (name "Net-(X1.5F-S)") (class "Default")
      (node (ref "JP38") (pin "1") (pinfunction "1_1") (pintype "passive"))
      (node (ref "X1.5") (pin "6") (pinfunction "S_6") (pintype "passive"))
      (node (ref "X5") (pin "6") (pinfunction "6_6") (pintype "passive"))
    )
    (net (code "56") (name "Net-(X1.5G-S)") (class "Default")
      (node (ref "JP39") (pin "1") (pinfunction "1_1") (pintype "passive"))
      (node (ref "X1.5") (pin "7") (pinfunction "S_7") (pintype "passive"))
      (node (ref "X5") (pin "7") (pinfunction "7_7") (pintype "passive"))
    )
    (net (code "57") (name "Net-(X1.5H-S)") (class "Default")
      (node (ref "JP40") (pin "1") (pinfunction "1_1") (pintype "passive"))
      (node (ref "X1.5") (pin "8") (pinfunction "S_8") (pintype "passive"))
      (node (ref "X5") (pin "8") (pinfunction "8_8") (pintype "passive"))
    )
    (net (code "58") (name "Net-(X1.6A-S)") (class "Default")
      (node (ref "JP41") (pin "1") (pinfunction "1_1") (pintype "passive"))
      (node (ref "X1.6") (pin "1") (pinfunction "S_1") (pintype "passive"))
      (node (ref "X6") (pin "1") (pinfunction "1_1") (pintype "passive"))
    )
    (net (code "59") (name "Net-(X1.6B-S)") (class "Default")
      (node (ref "JP42") (pin "1") (pinfunction "1_1") (pintype "passive"))
      (node (ref "X1.6") (pin "2") (pinfunction "S_2") (pintype "passive"))
      (node (ref "X6") (pin "2") (pinfunction "2_2") (pintype "passive"))
    )
    (net (code "60") (name "Net-(X1.6C-S)") (class "Default")
      (node (ref "JP43") (pin "1") (pinfunction "1_1") (pintype "passive"))
      (node (ref "X1.6") (pin "3") (pinfunction "S_3") (pintype "passive"))
      (node (ref "X6") (pin "3") (pinfunction "3_3") (pintype "passive"))
    )
    (net (code "61") (name "Net-(X1.6D-S)") (class "Default")
      (node (ref "JP44") (pin "1") (pinfunction "1_1") (pintype "passive"))
      (node (ref "X1.6") (pin "4") (pinfunction "S_4") (pintype "passive"))
      (node (ref "X6") (pin "4") (pinfunction "4_4") (pintype "passive"))
    )
    (net (code "62") (name "Net-(X1.6E-S)") (class "Default")
      (node (ref "JP45") (pin "1") (pinfunction "1_1") (pintype "passive"))
      (node (ref "X1.6") (pin "5") (pinfunction "S_5") (pintype "passive"))
      (node (ref "X6") (pin "5") (pinfunction "5_5") (pintype "passive"))
    )
    (net (code "63") (name "Net-(X1.6F-S)") (class "Default")
      (node (ref "JP46") (pin "1") (pinfunction "1_1") (pintype "passive"))
      (node (ref "X1.6") (pin "6") (pinfunction "S_6") (pintype "passive"))
      (node (ref "X6") (pin "6") (pinfunction "6_6") (pintype "passive"))
    )
    (net (code "64") (name "Net-(X1.6G-S)") (class "Default")
      (node (ref "JP47") (pin "1") (pinfunction "1_1") (pintype "passive"))
      (node (ref "X1.6") (pin "7") (pinfunction "S_7") (pintype "passive"))
      (node (ref "X6") (pin "7") (pinfunction "7_7") (pintype "passive"))
    )
    (net (code "65") (name "Net-(X1.6H-S)") (class "Default")
      (node (ref "JP48") (pin "1") (pinfunction "1_1") (pintype "passive"))
      (node (ref "X1.6") (pin "8") (pinfunction "S_8") (pintype "passive"))
      (node (ref "X6") (pin "8") (pinfunction "8_8") (pintype "passive"))
    )
    (net (code "66") (name "unconnected-(IC1-GP3-Pad4)") (class "Default")
      (node (ref "IC1") (pin "4") (pinfunction "GP3_4") (pintype "input"))
    )
    (net (code "67") (name "unconnected-(IC1-GP4{slash}CLKOUT-Pad3)") (class "Default")
      (node (ref "IC1") (pin "3") (pinfunction "GP4/CLKOUT_3") (pintype "bidirectional"))
    )
    (net (code "68") (name "unconnected-(IC1-GP5{slash}CLKIN-Pad2)") (class "Default")
      (node (ref "IC1") (pin "2") (pinfunction "GP5/CLKIN_2") (pintype "bidirectional"))
    )
    (net (code "69") (name "unconnected-(X1-S-PadS3)") (class "Default")
      (node (ref "X1") (pin "S3") (pinfunction "S_S3") (pintype "passive"))
    )
    (net (code "70") (name "unconnected-(X1-S-PadS4)") (class "Default")
      (node (ref "X1") (pin "S4") (pinfunction "S_S4") (pintype "passive"))
    )
    (net (code "71") (name "unconnected-(X2-S-PadS3)") (class "Default")
      (node (ref "X2") (pin "S3") (pinfunction "S_S3") (pintype "passive"))
    )
    (net (code "72") (name "unconnected-(X2-S-PadS4)") (class "Default")
      (node (ref "X2") (pin "S4") (pinfunction "S_S4") (pintype "passive"))
    )
    (net (code "73") (name "unconnected-(X3-S-PadS3)") (class "Default")
      (node (ref "X3") (pin "S3") (pinfunction "S_S3") (pintype "passive"))
    )
    (net (code "74") (name "unconnected-(X3-S-PadS4)") (class "Default")
      (node (ref "X3") (pin "S4") (pinfunction "S_S4") (pintype "passive"))
    )
    (net (code "75") (name "unconnected-(X4-S-PadS3)") (class "Default")
      (node (ref "X4") (pin "S3") (pinfunction "S_S3") (pintype "passive"))
    )
    (net (code "76") (name "unconnected-(X4-S-PadS4)") (class "Default")
      (node (ref "X4") (pin "S4") (pinfunction "S_S4") (pintype "passive"))
    )
    (net (code "77") (name "unconnected-(X5-S-PadS3)") (class "Default")
      (node (ref "X5") (pin "S3") (pinfunction "S_S3") (pintype "passive"))
    )
    (net (code "78") (name "unconnected-(X5-S-PadS4)") (class "Default")
      (node (ref "X5") (pin "S4") (pinfunction "S_S4") (pintype "passive"))
    )
    (net (code "79") (name "unconnected-(X6-S-PadS3)") (class "Default")
      (node (ref "X6") (pin "S3") (pinfunction "S_S3") (pintype "passive"))
    )
    (net (code "80") (name "unconnected-(X6-S-PadS4)") (class "Default")
      (node (ref "X6") (pin "S4") (pinfunction "S_S4") (pintype "passive"))
    )
  )
)
